# Logic_level_converter.net
KiCad netlist of a schematic drawn in EAGLE
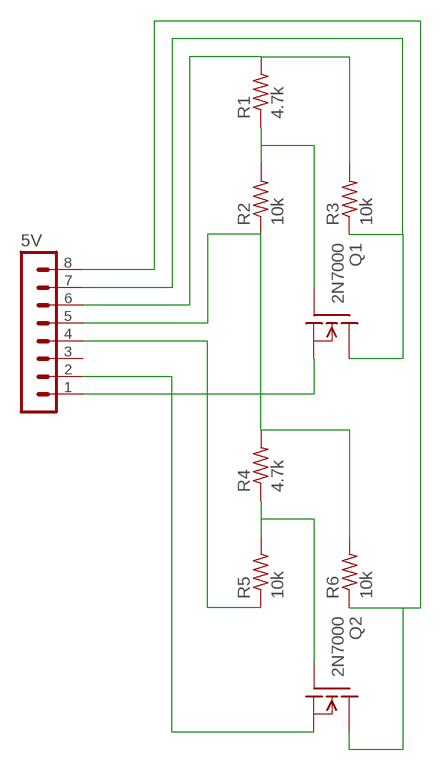
[diagram p0: schematic, sheet 1]

(export (version "E")
  (design (tool "Eeschema 10.0.6"))
  (components
    (comp (ref "5V")
      (value "MA08-1W")
      (footprint "eagle-import:MA08-1W")
      (libsource (lib "eagle-import") (part "MA08-1W"))
    )
    (comp (ref "Q1")
      (value "2N7000")
      (footprint "eagle-import:TO92")
      (libsource (lib "eagle-import") (part "BSS101"))
    )
    (comp (ref "Q2")
      (value "2N7000")
      (footprint "eagle-import:TO92")
      (libsource (lib "eagle-import") (part "BSS101"))
    )
    (comp (ref "R1")
      (value "4.7k")
      (footprint "eagle-import:0204V")
      (libsource (lib "eagle-import") (part "R-US_0204/2V"))
    )
    (comp (ref "R2")
      (value "10k")
      (footprint "eagle-import:0204V")
      (libsource (lib "eagle-import") (part "R-US_0204/2V"))
    )
    (comp (ref "R3")
      (value "10k")
      (footprint "eagle-import:0204V")
      (libsource (lib "eagle-import") (part "R-US_0204/2V"))
    )
    (comp (ref "R4")
      (value "4.7k")
      (footprint "eagle-import:0204V")
      (libsource (lib "eagle-import") (part "R-US_0204/2V"))
    )
    (comp (ref "R5")
      (value "10k")
      (footprint "eagle-import:0204V")
      (libsource (lib "eagle-import") (part "R-US_0204/2V"))
    )
    (comp (ref "R6")
      (value "10k")
      (footprint "eagle-import:0204V")
      (libsource (lib "eagle-import") (part "R-US_0204/2V"))
    )
  )
  (nets
    (net (code "1") (name "Net-(5V-Pad4)") (class "Default")
      (node (ref "5V") (pin "4") (pinfunction "4_4") (pintype "passive"))
      (node (ref "R5") (pin "1") (pinfunction "1_1") (pintype "passive"))
    )
    (net (code "2") (name "Net-(5V-Pad5)") (class "Default")
      (node (ref "5V") (pin "5") (pinfunction "5_5") (pintype "passive"))
      (node (ref "R2") (pin "1") (pinfunction "1_1") (pintype "passive"))
      (node (ref "R4") (pin "2") (pinfunction "2_2") (pintype "passive"))
      (node (ref "R6") (pin "2") (pinfunction "2_2") (pintype "passive"))
    )
    (net (code "3") (name "Net-(5V-Pad6)") (class "Default")
      (node (ref "5V") (pin "6") (pinfunction "6_6") (pintype "passive"))
      (node (ref "R1") (pin "2") (pinfunction "2_2") (pintype "passive"))
      (node (ref "R3") (pin "2") (pinfunction "2_2") (pintype "passive"))
    )
    (net (code "4") (name "Net-(Q1-D)") (class "Default")
      (node (ref "5V") (pin "7") (pinfunction "7_7") (pintype "passive"))
      (node (ref "Q1") (pin "3") (pinfunction "D_3") (pintype "passive"))
      (node (ref "R3") (pin "1") (pinfunction "1_1") (pintype "passive"))
    )
    (net (code "5") (name "Net-(Q1-G)") (class "Default")
      (node (ref "Q1") (pin "2") (pinfunction "G_2") (pintype "passive"))
      (node (ref "R1") (pin "1") (pinfunction "1_1") (pintype "passive"))
      (node (ref "R2") (pin "2") (pinfunction "2_2") (pintype "passive"))
    )
    (net (code "6") (name "Net-(Q1-S)") (class "Default")
      (node (ref "5V") (pin "1") (pinfunction "1_1") (pintype "passive"))
      (node (ref "Q1") (pin "1") (pinfunction "S_1") (pintype "passive"))
    )
    (net (code "7") (name "Net-(Q2-D)") (class "Default")
      (node (ref "5V") (pin "8") (pinfunction "8_8") (pintype "passive"))
      (node (ref "Q2") (pin "3") (pinfunction "D_3") (pintype "passive"))
      (node (ref "R6") (pin "1") (pinfunction "1_1") (pintype "passive"))
    )
    (net (code "8") (name "Net-(Q2-G)") (class "Default")
      (node (ref "Q2") (pin "2") (pinfunction "G_2") (pintype "passive"))
      (node (ref "R4") (pin "1") (pinfunction "1_1") (pintype "passive"))
      (node (ref "R5") (pin "2") (pinfunction "2_2") (pintype "passive"))
    )
    (net (code "9") (name "Net-(Q2-S)") (class "Default")
      (node (ref "5V") (pin "2") (pinfunction "2_2") (pintype "passive"))
      (node (ref "Q2") (pin "1") (pinfunction "S_1") (pintype "passive"))
    )
    (net (code "10") (name "unconnected-(5V-Pad3)") (class "Default")
      (node (ref "5V") (pin "3") (pinfunction "3_3") (pintype "passive"))
    )
  )
)
